# Power.net
KiCad netlist of a schematic drawn in Altium Designer
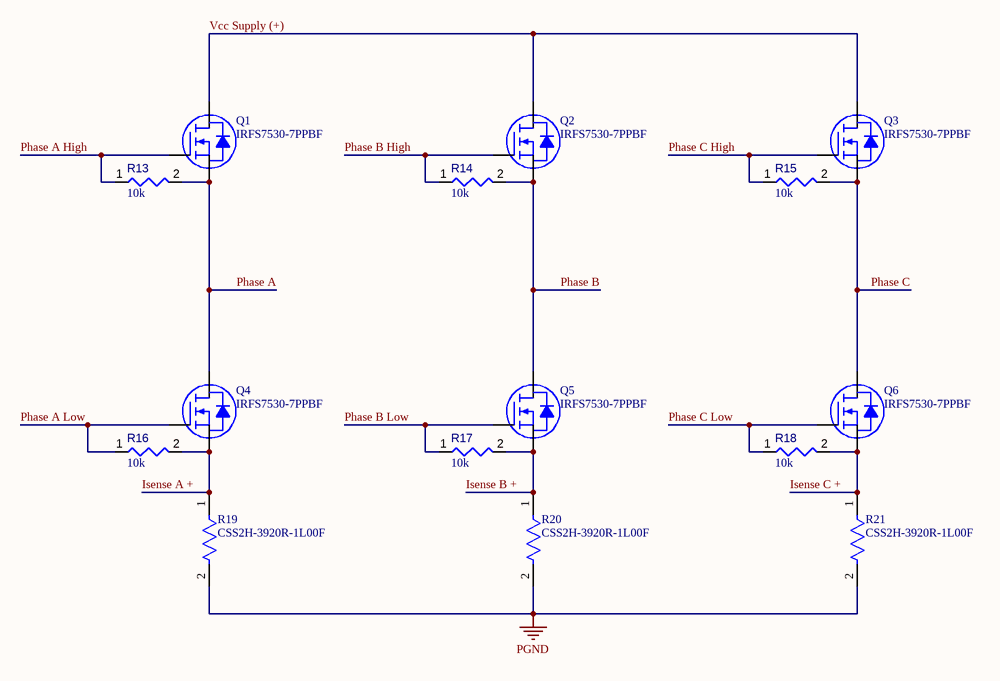
[diagram p0: Power.SchDoc]

(export (version "E")
  (design (tool "Eeschema 10.0.6"))
  (components
    (comp (ref "Q1")
      (value "IRFS7530-7PPBF")
      (footprint "INFINEON TO-263-7")
      (description "MOSFET N CH 60V 240A D2PAK")
      (fields
        (field (name "PART NUMBER") "IRFS7530TRL7PP")
        (field (name "MANUFACTURER") "Infineon Technologies")
      )
      (libsource (lib "Celestial Altium Library - altium_library") (part "INFINEON MOSFET N-CH TO263-7"))
    )
    (comp (ref "Q2")
      (value "IRFS7530-7PPBF")
      (footprint "INFINEON TO-263-7")
      (description "MOSFET N CH 60V 240A D2PAK")
      (fields
        (field (name "PART NUMBER") "IRFS7530TRL7PP")
        (field (name "MANUFACTURER") "Infineon Technologies")
      )
      (libsource (lib "Celestial Altium Library - altium_library") (part "INFINEON MOSFET N-CH TO263-7"))
    )
    (comp (ref "Q3")
      (value "IRFS7530-7PPBF")
      (footprint "INFINEON TO-263-7")
      (description "MOSFET N CH 60V 240A D2PAK")
      (fields
        (field (name "PART NUMBER") "IRFS7530TRL7PP")
        (field (name "MANUFACTURER") "Infineon Technologies")
      )
      (libsource (lib "Celestial Altium Library - altium_library") (part "INFINEON MOSFET N-CH TO263-7"))
    )
    (comp (ref "Q4")
      (value "IRFS7530-7PPBF")
      (footprint "INFINEON TO-263-7")
      (description "MOSFET N CH 60V 240A D2PAK")
      (fields
        (field (name "PART NUMBER") "IRFS7530TRL7PP")
        (field (name "MANUFACTURER") "Infineon Technologies")
      )
      (libsource (lib "Celestial Altium Library - altium_library") (part "INFINEON MOSFET N-CH TO263-7"))
    )
    (comp (ref "Q5")
      (value "IRFS7530-7PPBF")
      (footprint "INFINEON TO-263-7")
      (description "MOSFET N CH 60V 240A D2PAK")
      (fields
        (field (name "PART NUMBER") "IRFS7530TRL7PP")
        (field (name "MANUFACTURER") "Infineon Technologies")
      )
      (libsource (lib "Celestial Altium Library - altium_library") (part "INFINEON MOSFET N-CH TO263-7"))
    )
    (comp (ref "Q6")
      (value "IRFS7530-7PPBF")
      (footprint "INFINEON TO-263-7")
      (description "MOSFET N CH 60V 240A D2PAK")
      (fields
        (field (name "PART NUMBER") "IRFS7530TRL7PP")
        (field (name "MANUFACTURER") "Infineon Technologies")
      )
      (libsource (lib "Celestial Altium Library - altium_library") (part "INFINEON MOSFET N-CH TO263-7"))
    )
    (comp (ref "R13")
      (value "10k")
      (footprint "RESA60-630X240")
      (description "10 kOhms ±1% 0.25W, 1/4W Through Hole Resistor Axial Metal Film")
      (fields (field (name "TOLERANCE") "1%") (field (name "POWER") "250mW"))
      (libsource (lib "Pessoal") (part "RES-2"))
    )
    (comp (ref "R14")
      (value "10k")
      (footprint "RESA60-630X240")
      (description "10 kOhms ±1% 0.25W, 1/4W Through Hole Resistor Axial Metal Film")
      (fields (field (name "TOLERANCE") "1%") (field (name "POWER") "250mW"))
      (libsource (lib "Pessoal") (part "RES-2"))
    )
    (comp (ref "R15")
      (value "10k")
      (footprint "RESA60-630X240")
      (description "10 kOhms ±1% 0.25W, 1/4W Through Hole Resistor Axial Metal Film")
      (fields (field (name "TOLERANCE") "1%") (field (name "POWER") "250mW"))
      (libsource (lib "Pessoal") (part "RES-2"))
    )
    (comp (ref "R16")
      (value "10k")
      (footprint "RESA60-630X240")
      (description "10 kOhms ±1% 0.25W, 1/4W Through Hole Resistor Axial Metal Film")
      (fields (field (name "TOLERANCE") "1%") (field (name "POWER") "250mW"))
      (libsource (lib "Pessoal") (part "RES-2"))
    )
    (comp (ref "R17")
      (value "10k")
      (footprint "RESA60-630X240")
      (description "10 kOhms ±1% 0.25W, 1/4W Through Hole Resistor Axial Metal Film")
      (fields (field (name "TOLERANCE") "1%") (field (name "POWER") "250mW"))
      (libsource (lib "Pessoal") (part "RES-2"))
    )
    (comp (ref "R18")
      (value "10k")
      (footprint "RESA60-630X240")
      (description "10 kOhms ±1% 0.25W, 1/4W Through Hole Resistor Axial Metal Film")
      (fields (field (name "TOLERANCE") "1%") (field (name "POWER") "250mW"))
      (libsource (lib "Pessoal") (part "RES-2"))
    )
    (comp (ref "R19")
      (value "CSS2H-3920R-1L00F")
      (footprint "FP-CSS2H-3920R-1L00F-MFG")
      (description "RES 0.001 OHM 1% 8W 3920")
      (fields (field (name "TOLERANCE") "1%"))
      (libsource (lib "Altium Content Vault") (part "1029c3af85768c4190bb7ad29bc67b5"))
    )
    (comp (ref "R20")
      (value "CSS2H-3920R-1L00F")
      (footprint "FP-CSS2H-3920R-1L00F-MFG")
      (description "RES 0.001 OHM 1% 8W 3920")
      (fields (field (name "TOLERANCE") "1%"))
      (libsource (lib "Altium Content Vault") (part "1029c3af85768c4190bb7ad29bc67b5"))
    )
    (comp (ref "R21")
      (value "CSS2H-3920R-1L00F")
      (footprint "FP-CSS2H-3920R-1L00F-MFG")
      (description "RES 0.001 OHM 1% 8W 3920")
      (fields (field (name "TOLERANCE") "1%"))
      (libsource (lib "Altium Content Vault") (part "1029c3af85768c4190bb7ad29bc67b5"))
    )
  )
  (nets
    (net (code "1") (name "/Isense A +") (class "Default")
      (node (ref "Q4") (pin "2") (pinfunction "S_2") (pintype "passive"))
      (node (ref "Q4") (pin "3") (pinfunction "S_3") (pintype "passive"))
      (node (ref "Q4") (pin "5") (pinfunction "S_5") (pintype "passive"))
      (node (ref "Q4") (pin "6") (pinfunction "S_6") (pintype "passive"))
      (node (ref "Q4") (pin "7") (pinfunction "S_7") (pintype "passive"))
      (node (ref "R16") (pin "2") (pinfunction "2_2") (pintype "passive"))
      (node (ref "R19") (pin "1") (pinfunction "1_1") (pintype "passive"))
    )
    (net (code "2") (name "/Isense B +") (class "Default")
      (node (ref "Q5") (pin "2") (pinfunction "S_2") (pintype "passive"))
      (node (ref "Q5") (pin "3") (pinfunction "S_3") (pintype "passive"))
      (node (ref "Q5") (pin "5") (pinfunction "S_5") (pintype "passive"))
      (node (ref "Q5") (pin "6") (pinfunction "S_6") (pintype "passive"))
      (node (ref "Q5") (pin "7") (pinfunction "S_7") (pintype "passive"))
      (node (ref "R17") (pin "2") (pinfunction "2_2") (pintype "passive"))
      (node (ref "R20") (pin "1") (pinfunction "1_1") (pintype "passive"))
    )
    (net (code "3") (name "/Isense C +") (class "Default")
      (node (ref "Q6") (pin "2") (pinfunction "S_2") (pintype "passive"))
      (node (ref "Q6") (pin "3") (pinfunction "S_3") (pintype "passive"))
      (node (ref "Q6") (pin "5") (pinfunction "S_5") (pintype "passive"))
      (node (ref "Q6") (pin "6") (pinfunction "S_6") (pintype "passive"))
      (node (ref "Q6") (pin "7") (pinfunction "S_7") (pintype "passive"))
      (node (ref "R18") (pin "2") (pinfunction "2_2") (pintype "passive"))
      (node (ref "R21") (pin "1") (pinfunction "1_1") (pintype "passive"))
    )
    (net (code "4") (name "/Phase A") (class "Default")
      (node (ref "Q1") (pin "2") (pinfunction "S_2") (pintype "passive"))
      (node (ref "Q1") (pin "3") (pinfunction "S_3") (pintype "passive"))
      (node (ref "Q1") (pin "5") (pinfunction "S_5") (pintype "passive"))
      (node (ref "Q1") (pin "6") (pinfunction "S_6") (pintype "passive"))
      (node (ref "Q1") (pin "7") (pinfunction "S_7") (pintype "passive"))
      (node (ref "Q4") (pin "8") (pinfunction "D_8") (pintype "passive"))
      (node (ref "R13") (pin "2") (pinfunction "2_2") (pintype "passive"))
    )
    (net (code "5") (name "/Phase A High") (class "Default")
      (node (ref "Q1") (pin "1") (pinfunction "G_1") (pintype "passive"))
      (node (ref "R13") (pin "1") (pinfunction "1_1") (pintype "passive"))
    )
    (net (code "6") (name "/Phase A Low") (class "Default")
      (node (ref "Q4") (pin "1") (pinfunction "G_1") (pintype "passive"))
      (node (ref "R16") (pin "1") (pinfunction "1_1") (pintype "passive"))
    )
    (net (code "7") (name "/Phase B") (class "Default")
      (node (ref "Q2") (pin "2") (pinfunction "S_2") (pintype "passive"))
      (node (ref "Q2") (pin "3") (pinfunction "S_3") (pintype "passive"))
      (node (ref "Q2") (pin "5") (pinfunction "S_5") (pintype "passive"))
      (node (ref "Q2") (pin "6") (pinfunction "S_6") (pintype "passive"))
      (node (ref "Q2") (pin "7") (pinfunction "S_7") (pintype "passive"))
      (node (ref "Q5") (pin "8") (pinfunction "D_8") (pintype "passive"))
      (node (ref "R14") (pin "2") (pinfunction "2_2") (pintype "passive"))
    )
    (net (code "8") (name "/Phase B High") (class "Default")
      (node (ref "Q2") (pin "1") (pinfunction "G_1") (pintype "passive"))
      (node (ref "R14") (pin "1") (pinfunction "1_1") (pintype "passive"))
    )
    (net (code "9") (name "/Phase B Low") (class "Default")
      (node (ref "Q5") (pin "1") (pinfunction "G_1") (pintype "passive"))
      (node (ref "R17") (pin "1") (pinfunction "1_1") (pintype "passive"))
    )
    (net (code "10") (name "/Phase C") (class "Default")
      (node (ref "Q3") (pin "2") (pinfunction "S_2") (pintype "passive"))
      (node (ref "Q3") (pin "3") (pinfunction "S_3") (pintype "passive"))
      (node (ref "Q3") (pin "5") (pinfunction "S_5") (pintype "passive"))
      (node (ref "Q3") (pin "6") (pinfunction "S_6") (pintype "passive"))
      (node (ref "Q3") (pin "7") (pinfunction "S_7") (pintype "passive"))
      (node (ref "Q6") (pin "8") (pinfunction "D_8") (pintype "passive"))
      (node (ref "R15") (pin "2") (pinfunction "2_2") (pintype "passive"))
    )
    (net (code "11") (name "/Phase C High") (class "Default")
      (node (ref "Q3") (pin "1") (pinfunction "G_1") (pintype "passive"))
      (node (ref "R15") (pin "1") (pinfunction "1_1") (pintype "passive"))
    )
    (net (code "12") (name "/Phase C Low") (class "Default")
      (node (ref "Q6") (pin "1") (pinfunction "G_1") (pintype "passive"))
      (node (ref "R18") (pin "1") (pinfunction "1_1") (pintype "passive"))
    )
    (net (code "13") (name "/Vcc Supply (+)") (class "Default")
      (node (ref "Q1") (pin "8") (pinfunction "D_8") (pintype "passive"))
      (node (ref "Q2") (pin "8") (pinfunction "D_8") (pintype "passive"))
      (node (ref "Q3") (pin "8") (pinfunction "D_8") (pintype "passive"))
    )
    (net (code "14") (name "PGND") (class "Default")
      (node (ref "R19") (pin "2") (pinfunction "2_2") (pintype "passive"))
      (node (ref "R20") (pin "2") (pinfunction "2_2") (pintype "passive"))
      (node (ref "R21") (pin "2") (pinfunction "2_2") (pintype "passive"))
    )
  )
)
